# BW1092_RIGHT_OV9282.net
KiCad netlist of a schematic drawn in Altium Designer
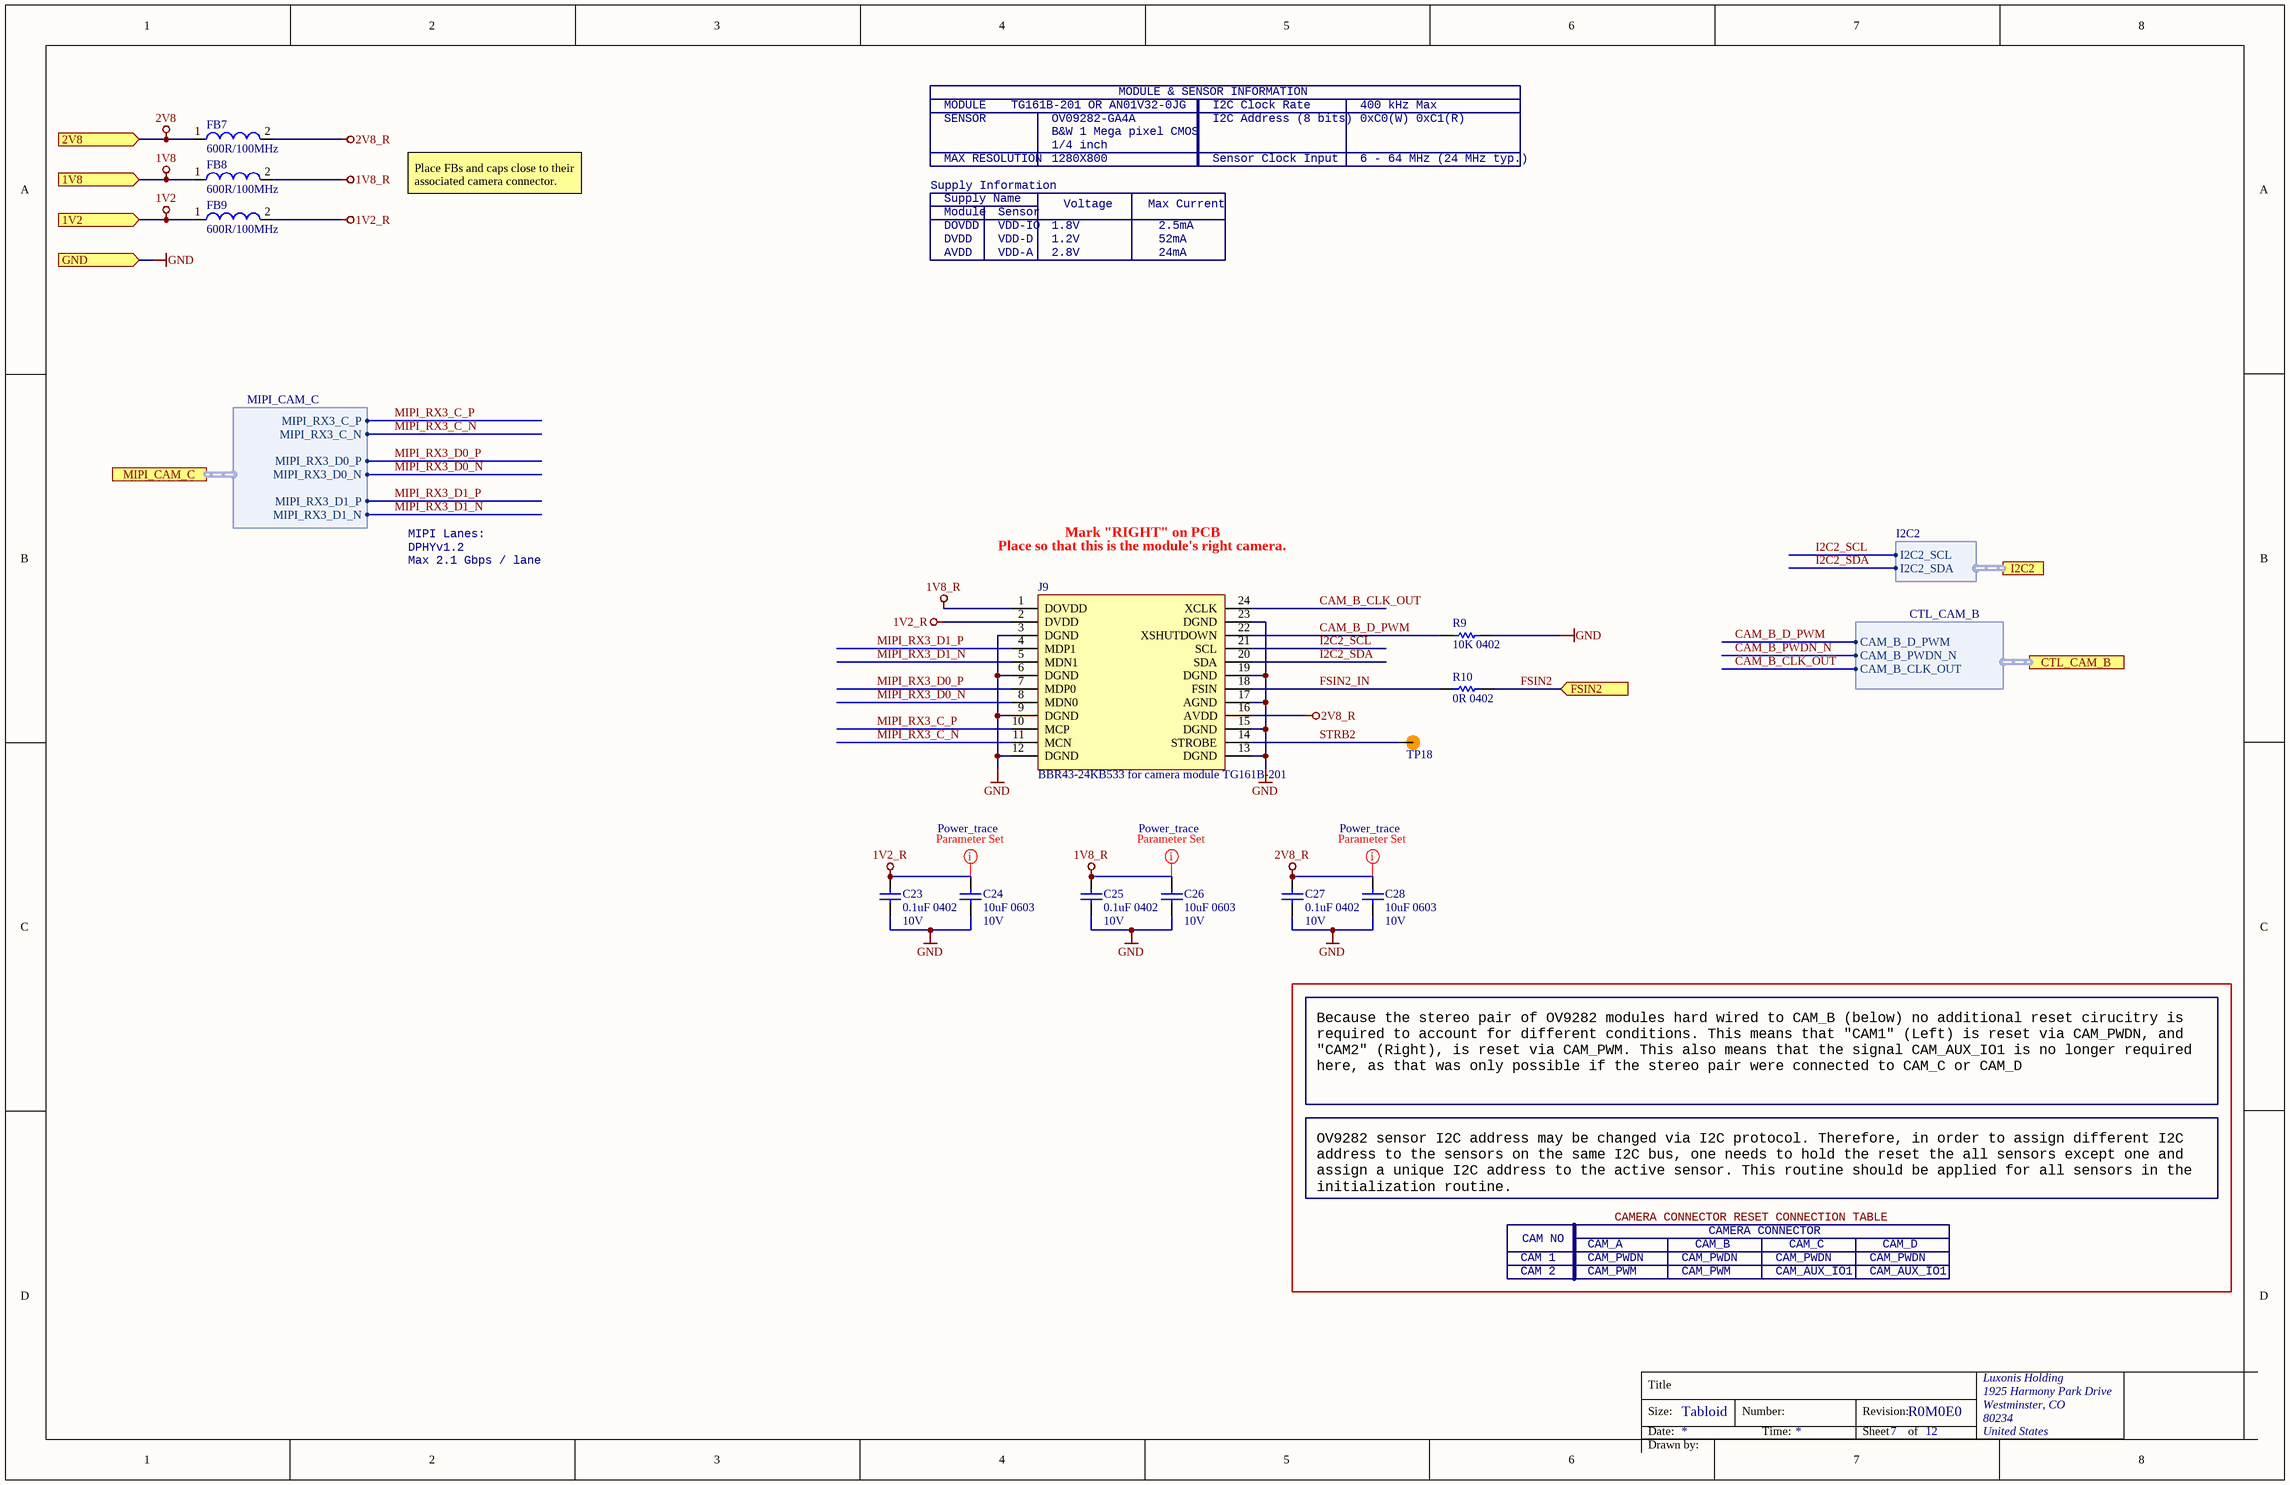
[diagram p0: BW1092_RIGHT_OV9282.SchDoc]

(export (version "E")
  (design (tool "Eeschema 10.0.6"))
  (components
    (comp (ref "C23")
      (value "0.1uF 0402")
      (footprint "CAP_Altium_Vault_Generic:CAPC0402(1005)70_L")
      (description "CAP CER 0.1UF 10V X7R 0402 5%")
      (fields (field (name "TOLERANCE") "5%") (field (name "VOLTAGE RATING") "10V"))
      (libsource (lib "LuxonisMaster") (part "GRM155R71A104JA01D"))
    )
    (comp (ref "C24")
      (value "10uF 0603")
      (footprint "CAP_Altium_Vault_Generic:CAPC0603(1608)100_L")
      (description "CAP CER 10UF 10V X5R 0603 20%")
      (fields (field (name "TOLERANCE") "20%") (field (name "VOLTAGE RATING") "10V"))
      (libsource (lib "LuxonisMaster") (part "GRM188R61A106ME69D"))
    )
    (comp (ref "C25")
      (value "0.1uF 0402")
      (footprint "CAP_Altium_Vault_Generic:CAPC0402(1005)70_L")
      (description "CAP CER 0.1UF 10V X7R 0402 5%")
      (fields (field (name "TOLERANCE") "5%") (field (name "VOLTAGE RATING") "10V"))
      (libsource (lib "LuxonisMaster") (part "GRM155R71A104JA01D"))
    )
    (comp (ref "C26")
      (value "10uF 0603")
      (footprint "CAP_Altium_Vault_Generic:CAPC0603(1608)100_L")
      (description "CAP CER 10UF 10V X5R 0603 20%")
      (fields (field (name "TOLERANCE") "20%") (field (name "VOLTAGE RATING") "10V"))
      (libsource (lib "LuxonisMaster") (part "GRM188R61A106ME69D"))
    )
    (comp (ref "C27")
      (value "0.1uF 0402")
      (footprint "CAP_Altium_Vault_Generic:CAPC0402(1005)70_L")
      (description "CAP CER 0.1UF 10V X7R 0402 5%")
      (fields (field (name "TOLERANCE") "5%") (field (name "VOLTAGE RATING") "10V"))
      (libsource (lib "LuxonisMaster") (part "GRM155R71A104JA01D"))
    )
    (comp (ref "C28")
      (value "10uF 0603")
      (footprint "CAP_Altium_Vault_Generic:CAPC0603(1608)100_L")
      (description "CAP CER 10UF 10V X5R 0603 20%")
      (fields (field (name "TOLERANCE") "20%") (field (name "VOLTAGE RATING") "10V"))
      (libsource (lib "LuxonisMaster") (part "GRM188R61A106ME69D"))
    )
    (comp (ref "FB7")
      (value "600R/100MHz")
      (footprint "LuxonisMaster:2508056017Y2")
      (description "FERRITE BEAD, 0.1OHM, 2A, 0805, 600R/100MHz")
      (fields (field (name "TOLERANCE") "25%"))
      (libsource (lib "LuxonisMaster") (part "2508056017Y2"))
    )
    (comp (ref "FB8")
      (value "600R/100MHz")
      (footprint "LuxonisMaster:2508056017Y2")
      (description "FERRITE BEAD, 0.1OHM, 2A, 0805, 600R/100MHz")
      (fields (field (name "TOLERANCE") "25%"))
      (libsource (lib "LuxonisMaster") (part "2508056017Y2"))
    )
    (comp (ref "FB9")
      (value "600R/100MHz")
      (footprint "LuxonisMaster:2508056017Y2")
      (description "FERRITE BEAD, 0.1OHM, 2A, 0805, 600R/100MHz")
      (fields (field (name "TOLERANCE") "25%"))
      (libsource (lib "LuxonisMaster") (part "2508056017Y2"))
    )
    (comp (ref "J9")
      (value "BBR43-24KB533 for camera module TG161B-201")
      (footprint "LuxonisMaster:TG161B-201_HD")
      (description "CONN 24 way, 2 row board to board connector SMD")
      (libsource (lib "LuxonisMaster") (part "TG161B-201_Connector"))
    )
    (comp (ref "R9")
      (value "10K 0402")
      (footprint "RES_Altium_Vault_Generic:RESC0402(1005)_L")
      (fields (field (name "TOLERANCE") "1%"))
      (libsource (lib "LuxonisMaster") (part "RC0402FR-1310KL"))
    )
    (comp (ref "R10")
      (value "0R 0402")
      (footprint "RES_Altium_Vault_Generic:RESC0402(1005)_L")
      (description "RES SMD 0 OHM JUMPER 1/16W 0402")
      (fields (field (name "TOLERANCE") "5%"))
      (libsource (lib "LuxonisMaster") (part "CRCW04020000Z0ED"))
    )
    (comp (ref "TP18")
      (value "TP100_200_NS")
      (footprint "LuxonisMaster:TP100_200_NS")
      (libsource (lib "LuxonisMaster") (part "TEST_POINT"))
    )
  )
  (nets
    (net (code "4") (name "/CAM_B_CLK_OUT") (class "Default")
      (node (ref "J9") (pin "24") (pinfunction "XCLK_24") (pintype "passive"))
    )
    (net (code "5") (name "/CAM_B_D_PWM") (class "Default")
      (node (ref "J9") (pin "22") (pinfunction "XSHUTDOWN_22") (pintype "passive"))
      (node (ref "R9") (pin "1") (pinfunction "1_1") (pintype "passive"))
    )
    (net (code "7") (name "/FSIN2") (class "Default")
      (node (ref "R10") (pin "2") (pinfunction "2_2") (pintype "passive"))
    )
    (net (code "8") (name "/FSIN2_IN") (class "Default")
      (node (ref "J9") (pin "18") (pinfunction "FSIN_18") (pintype "passive"))
      (node (ref "R10") (pin "1") (pinfunction "1_1") (pintype "passive"))
    )
    (net (code "9") (name "/I2C2_SCL") (class "Default")
      (node (ref "J9") (pin "21") (pinfunction "SCL_21") (pintype "passive"))
    )
    (net (code "10") (name "/I2C2_SDA") (class "Default")
      (node (ref "J9") (pin "20") (pinfunction "SDA_20") (pintype "passive"))
    )
    (net (code "11") (name "/MIPI_RX3_C_N") (class "Default")
      (node (ref "J9") (pin "11") (pinfunction "MCN_11") (pintype "passive"))
    )
    (net (code "12") (name "/MIPI_RX3_C_P") (class "Default")
      (node (ref "J9") (pin "10") (pinfunction "MCP_10") (pintype "passive"))
    )
    (net (code "13") (name "/MIPI_RX3_D0_N") (class "Default")
      (node (ref "J9") (pin "8") (pinfunction "MDN0_8") (pintype "passive"))
    )
    (net (code "14") (name "/MIPI_RX3_D0_P") (class "Default")
      (node (ref "J9") (pin "7") (pinfunction "MDP0_7") (pintype "passive"))
    )
    (net (code "15") (name "/MIPI_RX3_D1_N") (class "Default")
      (node (ref "J9") (pin "5") (pinfunction "MDN1_5") (pintype "passive"))
    )
    (net (code "16") (name "/MIPI_RX3_D1_P") (class "Default")
      (node (ref "J9") (pin "4") (pinfunction "MDP1_4") (pintype "passive"))
    )
    (net (code "17") (name "/STRB2") (class "Default")
      (node (ref "J9") (pin "14") (pinfunction "STROBE_14") (pintype "passive"))
      (node (ref "TP18") (pin "1") (pintype "passive"))
    )
    (net (code "21") (name "1V2") (class "Default")
      (node (ref "FB9") (pin "1") (pinfunction "1_1") (pintype "passive"))
    )
    (net (code "22") (name "1V2_R") (class "Default")
      (node (ref "C23") (pin "2") (pinfunction "2_2") (pintype "passive"))
      (node (ref "C24") (pin "2") (pinfunction "2_2") (pintype "passive"))
      (node (ref "FB9") (pin "2") (pinfunction "2_2") (pintype "passive"))
      (node (ref "J9") (pin "2") (pinfunction "DVDD_2") (pintype "passive"))
    )
    (net (code "23") (name "1V8") (class "Default")
      (node (ref "FB8") (pin "1") (pinfunction "1_1") (pintype "passive"))
    )
    (net (code "24") (name "1V8_R") (class "Default")
      (node (ref "C25") (pin "2") (pinfunction "2_2") (pintype "passive"))
      (node (ref "C26") (pin "2") (pinfunction "2_2") (pintype "passive"))
      (node (ref "FB8") (pin "2") (pinfunction "2_2") (pintype "passive"))
      (node (ref "J9") (pin "1") (pinfunction "DOVDD_1") (pintype "passive"))
    )
    (net (code "25") (name "2V8") (class "Default")
      (node (ref "FB7") (pin "1") (pinfunction "1_1") (pintype "passive"))
    )
    (net (code "26") (name "2V8_R") (class "Default")
      (node (ref "C27") (pin "2") (pinfunction "2_2") (pintype "passive"))
      (node (ref "C28") (pin "2") (pinfunction "2_2") (pintype "passive"))
      (node (ref "FB7") (pin "2") (pinfunction "2_2") (pintype "passive"))
      (node (ref "J9") (pin "16") (pinfunction "AVDD_16") (pintype "passive"))
    )
    (net (code "27") (name "GND") (class "Default")
      (node (ref "C23") (pin "1") (pinfunction "1_1") (pintype "passive"))
      (node (ref "C24") (pin "1") (pinfunction "1_1") (pintype "passive"))
      (node (ref "C25") (pin "1") (pinfunction "1_1") (pintype "passive"))
      (node (ref "C26") (pin "1") (pinfunction "1_1") (pintype "passive"))
      (node (ref "C27") (pin "1") (pinfunction "1_1") (pintype "passive"))
      (node (ref "C28") (pin "1") (pinfunction "1_1") (pintype "passive"))
      (node (ref "J9") (pin "12") (pinfunction "DGND_12") (pintype "passive"))
      (node (ref "J9") (pin "13") (pinfunction "DGND_13") (pintype "passive"))
      (node (ref "J9") (pin "15") (pinfunction "DGND_15") (pintype "passive"))
      (node (ref "J9") (pin "17") (pinfunction "AGND_17") (pintype "passive"))
      (node (ref "J9") (pin "19") (pinfunction "DGND_19") (pintype "passive"))
      (node (ref "J9") (pin "23") (pinfunction "DGND_23") (pintype "passive"))
      (node (ref "J9") (pin "3") (pinfunction "DGND_3") (pintype "passive"))
      (node (ref "J9") (pin "6") (pinfunction "DGND_6") (pintype "passive"))
      (node (ref "J9") (pin "9") (pinfunction "DGND_9") (pintype "passive"))
      (node (ref "R9") (pin "2") (pinfunction "2_2") (pintype "passive"))
    )
  )
)
